# JTAG_SWD.net
KiCad netlist of a schematic drawn in Altium Designer
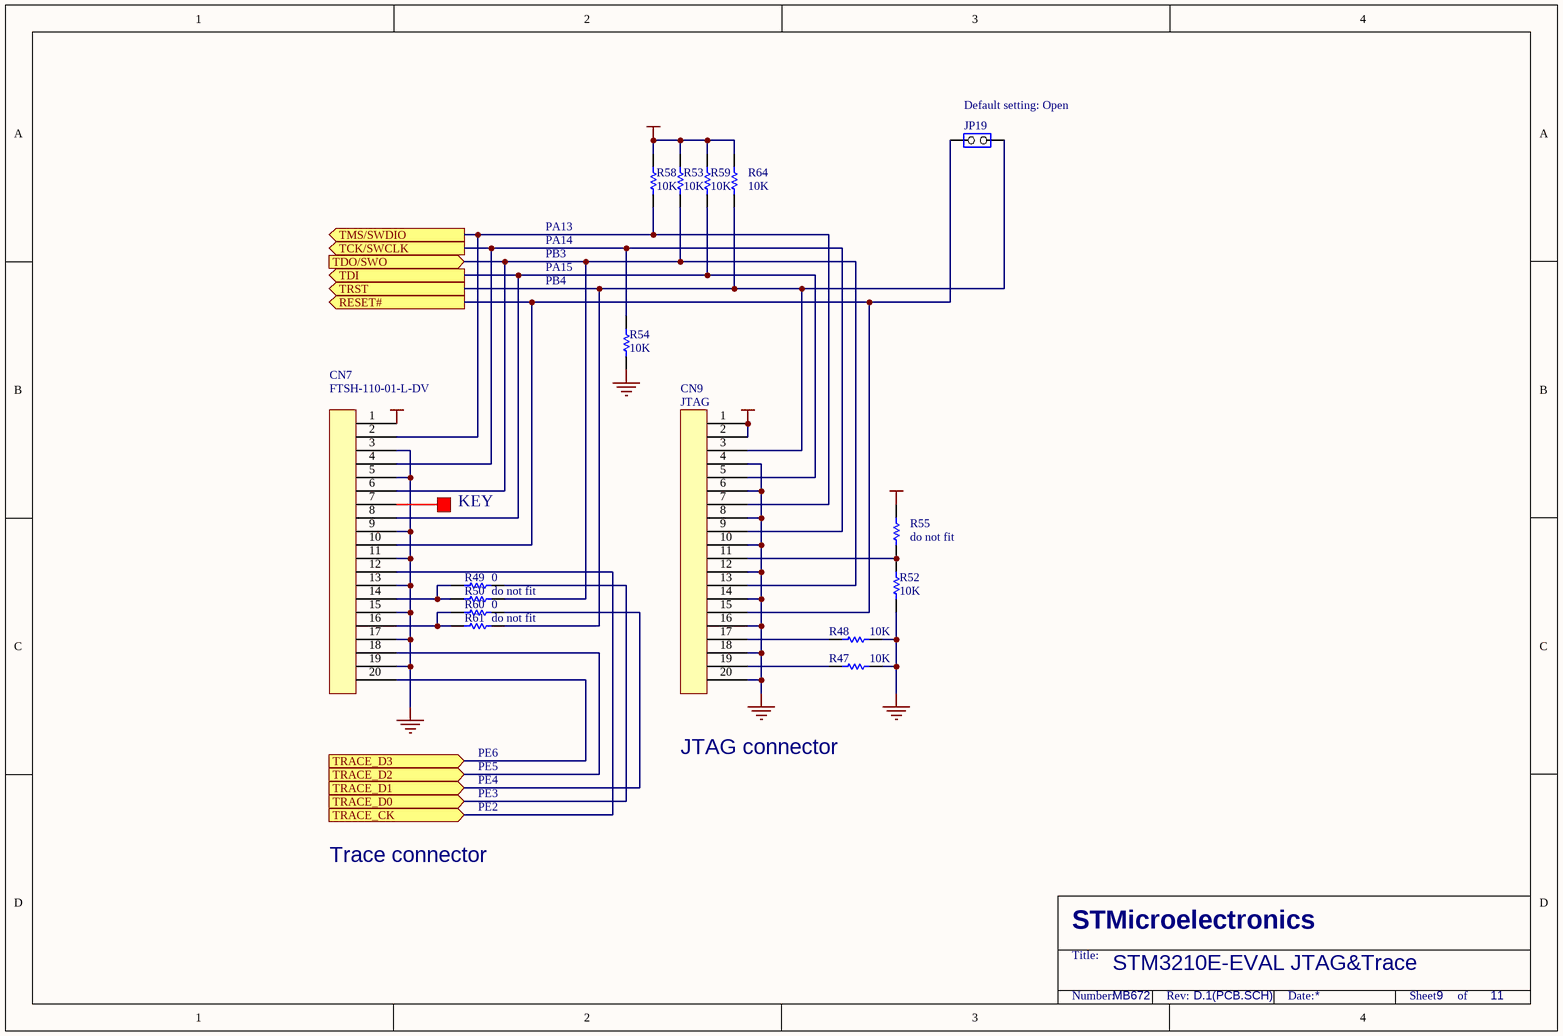
[diagram p0: JTAG&SWD.SchDoc]

(export (version "E")
  (design (tool "Eeschema 10.0.6"))
  (components
    (comp (ref "CN7") (value "FTSH-110-01-L-DV") (footprint "IDC20S") (libsource (lib "*") (part "20PIN1")))
    (comp (ref "CN9") (value "JTAG") (footprint "IDC20S") (libsource (lib "*") (part "20PIN1")))
    (comp (ref "JP19") (value "~") (footprint "SIP2") (libsource (lib "*") (part "JP2")))
    (comp (ref "R47")
      (value "10K")
      (description "Resistor")
      (fields (field (name "PUBLISHER") "Altium Limited"))
      (libsource (lib "Miscellaneous Devices") (part "Res1"))
    )
    (comp (ref "R48")
      (value "10K")
      (description "Resistor")
      (fields (field (name "PUBLISHER") "Altium Limited"))
      (libsource (lib "Miscellaneous Devices") (part "Res1"))
    )
    (comp (ref "R49")
      (value "0")
      (description "Resistor")
      (fields (field (name "PUBLISHER") "Altium Limited"))
      (libsource (lib "Miscellaneous Devices") (part "Res1"))
    )
    (comp (ref "R50")
      (value "do not fit")
      (description "Resistor")
      (fields (field (name "PUBLISHER") "Altium Limited"))
      (libsource (lib "Miscellaneous Devices") (part "Res1"))
    )
    (comp (ref "R52")
      (value "10K")
      (description "Resistor")
      (fields (field (name "PUBLISHER") "Altium Limited"))
      (libsource (lib "Miscellaneous Devices") (part "Res1"))
    )
    (comp (ref "R53")
      (value "10K")
      (description "Resistor")
      (fields (field (name "PUBLISHER") "Altium Limited"))
      (libsource (lib "Miscellaneous Devices") (part "Res1"))
    )
    (comp (ref "R54")
      (value "10K")
      (description "Resistor")
      (fields (field (name "PUBLISHER") "Altium Limited"))
      (libsource (lib "Miscellaneous Devices") (part "Res1"))
    )
    (comp (ref "R55")
      (value "do not fit")
      (description "Resistor")
      (fields (field (name "PUBLISHER") "Altium Limited"))
      (libsource (lib "Miscellaneous Devices") (part "Res1"))
    )
    (comp (ref "R58")
      (value "10K")
      (description "Resistor")
      (fields (field (name "PUBLISHER") "Altium Limited"))
      (libsource (lib "Miscellaneous Devices") (part "Res1"))
    )
    (comp (ref "R59")
      (value "10K")
      (description "Resistor")
      (fields (field (name "PUBLISHER") "Altium Limited"))
      (libsource (lib "Miscellaneous Devices") (part "Res1"))
    )
    (comp (ref "R60")
      (value "0")
      (description "Resistor")
      (fields (field (name "PUBLISHER") "Altium Limited"))
      (libsource (lib "Miscellaneous Devices") (part "Res1"))
    )
    (comp (ref "R61")
      (value "do not fit")
      (description "Resistor")
      (fields (field (name "PUBLISHER") "Altium Limited"))
      (libsource (lib "Miscellaneous Devices") (part "Res1"))
    )
    (comp (ref "R64")
      (value "10K")
      (description "Resistor")
      (fields (field (name "PUBLISHER") "Altium Limited"))
      (libsource (lib "Miscellaneous Devices") (part "Res1"))
    )
  )
  (nets
    (net (code "1") (name "+3V3") (class "Default")
      (node (ref "CN7") (pin "1") (pintype "passive"))
      (node (ref "CN9") (pin "1") (pintype "passive"))
      (node (ref "CN9") (pin "2") (pintype "passive"))
      (node (ref "R53") (pin "2") (pinfunction "2_2") (pintype "passive"))
      (node (ref "R55") (pin "2") (pinfunction "2_2") (pintype "passive"))
      (node (ref "R58") (pin "2") (pinfunction "2_2") (pintype "passive"))
      (node (ref "R59") (pin "2") (pinfunction "2_2") (pintype "passive"))
      (node (ref "R64") (pin "2") (pinfunction "2_2") (pintype "passive"))
    )
    (net (code "2") (name "/RESET#") (class "Default")
      (node (ref "CN7") (pin "10") (pintype "passive"))
      (node (ref "CN9") (pin "15") (pintype "passive"))
      (node (ref "JP19") (pin "2") (pinfunction "NO_2") (pintype "passive"))
    )
    (net (code "3") (name "/TCK{slash}SWCLK") (class "Default")
      (node (ref "CN7") (pin "4") (pintype "passive"))
      (node (ref "CN9") (pin "9") (pintype "passive"))
      (node (ref "R54") (pin "2") (pinfunction "2_2") (pintype "passive"))
    )
    (net (code "4") (name "/TDI") (class "Default")
      (node (ref "CN7") (pin "8") (pintype "passive"))
      (node (ref "CN9") (pin "5") (pintype "passive"))
      (node (ref "R59") (pin "1") (pinfunction "1_1") (pintype "passive"))
    )
    (net (code "5") (name "/TDO{slash}SWO") (class "Default")
      (node (ref "CN7") (pin "6") (pintype "passive"))
      (node (ref "CN9") (pin "13") (pintype "passive"))
      (node (ref "R50") (pin "2") (pinfunction "2_2") (pintype "passive"))
      (node (ref "R53") (pin "1") (pinfunction "1_1") (pintype "passive"))
    )
    (net (code "6") (name "/TMS{slash}SWDIO") (class "Default")
      (node (ref "CN7") (pin "2") (pintype "passive"))
      (node (ref "CN9") (pin "7") (pintype "passive"))
      (node (ref "R58") (pin "1") (pinfunction "1_1") (pintype "passive"))
    )
    (net (code "7") (name "/TRACE_CK") (class "Default") (node (ref "CN7") (pin "12") (pintype "passive")))
    (net (code "8") (name "/TRACE_D0") (class "Default")
      (node (ref "R49") (pin "2") (pinfunction "2_2") (pintype "passive"))
    )
    (net (code "9") (name "/TRACE_D1") (class "Default")
      (node (ref "R60") (pin "2") (pinfunction "2_2") (pintype "passive"))
    )
    (net (code "10") (name "/TRACE_D2") (class "Default") (node (ref "CN7") (pin "18") (pintype "passive")))
    (net (code "11") (name "/TRACE_D3") (class "Default") (node (ref "CN7") (pin "20") (pintype "passive")))
    (net (code "12") (name "/TRST") (class "Default")
      (node (ref "CN9") (pin "3") (pintype "passive"))
      (node (ref "JP19") (pin "1") (pinfunction "COMMON_1") (pintype "passive"))
      (node (ref "R61") (pin "2") (pinfunction "2_2") (pintype "passive"))
      (node (ref "R64") (pin "1") (pinfunction "1_1") (pintype "passive"))
    )
    (net (code "13") (name "GND") (class "Default")
      (node (ref "CN7") (pin "11") (pintype "passive"))
      (node (ref "CN7") (pin "13") (pintype "passive"))
      (node (ref "CN7") (pin "15") (pintype "passive"))
      (node (ref "CN7") (pin "17") (pintype "passive"))
      (node (ref "CN7") (pin "19") (pintype "passive"))
      (node (ref "CN7") (pin "3") (pintype "passive"))
      (node (ref "CN7") (pin "5") (pintype "passive"))
      (node (ref "CN7") (pin "9") (pintype "passive"))
      (node (ref "CN9") (pin "10") (pintype "passive"))
      (node (ref "CN9") (pin "12") (pintype "passive"))
      (node (ref "CN9") (pin "14") (pintype "passive"))
      (node (ref "CN9") (pin "16") (pintype "passive"))
      (node (ref "CN9") (pin "18") (pintype "passive"))
      (node (ref "CN9") (pin "20") (pintype "passive"))
      (node (ref "CN9") (pin "4") (pintype "passive"))
      (node (ref "CN9") (pin "6") (pintype "passive"))
      (node (ref "CN9") (pin "8") (pintype "passive"))
      (node (ref "R47") (pin "2") (pinfunction "2_2") (pintype "passive"))
      (node (ref "R48") (pin "2") (pinfunction "2_2") (pintype "passive"))
      (node (ref "R52") (pin "1") (pinfunction "1_1") (pintype "passive"))
      (node (ref "R54") (pin "1") (pinfunction "1_1") (pintype "passive"))
    )
    (net (code "14") (name "Net-(CN7-Pad14)") (class "Default")
      (node (ref "CN7") (pin "14") (pintype "passive"))
      (node (ref "R49") (pin "1") (pinfunction "1_1") (pintype "passive"))
      (node (ref "R50") (pin "1") (pinfunction "1_1") (pintype "passive"))
    )
    (net (code "15") (name "Net-(CN7-Pad16)") (class "Default")
      (node (ref "CN7") (pin "16") (pintype "passive"))
      (node (ref "R60") (pin "1") (pinfunction "1_1") (pintype "passive"))
      (node (ref "R61") (pin "1") (pinfunction "1_1") (pintype "passive"))
    )
    (net (code "16") (name "Net-(CN9-Pad11)") (class "Default")
      (node (ref "CN9") (pin "11") (pintype "passive"))
      (node (ref "R52") (pin "2") (pinfunction "2_2") (pintype "passive"))
      (node (ref "R55") (pin "1") (pinfunction "1_1") (pintype "passive"))
    )
    (net (code "17") (name "Net-(CN9-Pad17)") (class "Default")
      (node (ref "CN9") (pin "17") (pintype "passive"))
      (node (ref "R48") (pin "1") (pinfunction "1_1") (pintype "passive"))
    )
    (net (code "18") (name "Net-(CN9-Pad19)") (class "Default")
      (node (ref "CN9") (pin "19") (pintype "passive"))
      (node (ref "R47") (pin "1") (pinfunction "1_1") (pintype "passive"))
    )
    (net (code "19") (name "unconnected-(CN7-Pad7)") (class "Default")
      (node (ref "CN7") (pin "7") (pintype "passive"))
    )
  )
)
